# Sheet_PLC.net
KiCad netlist of a schematic drawn in Altium Designer
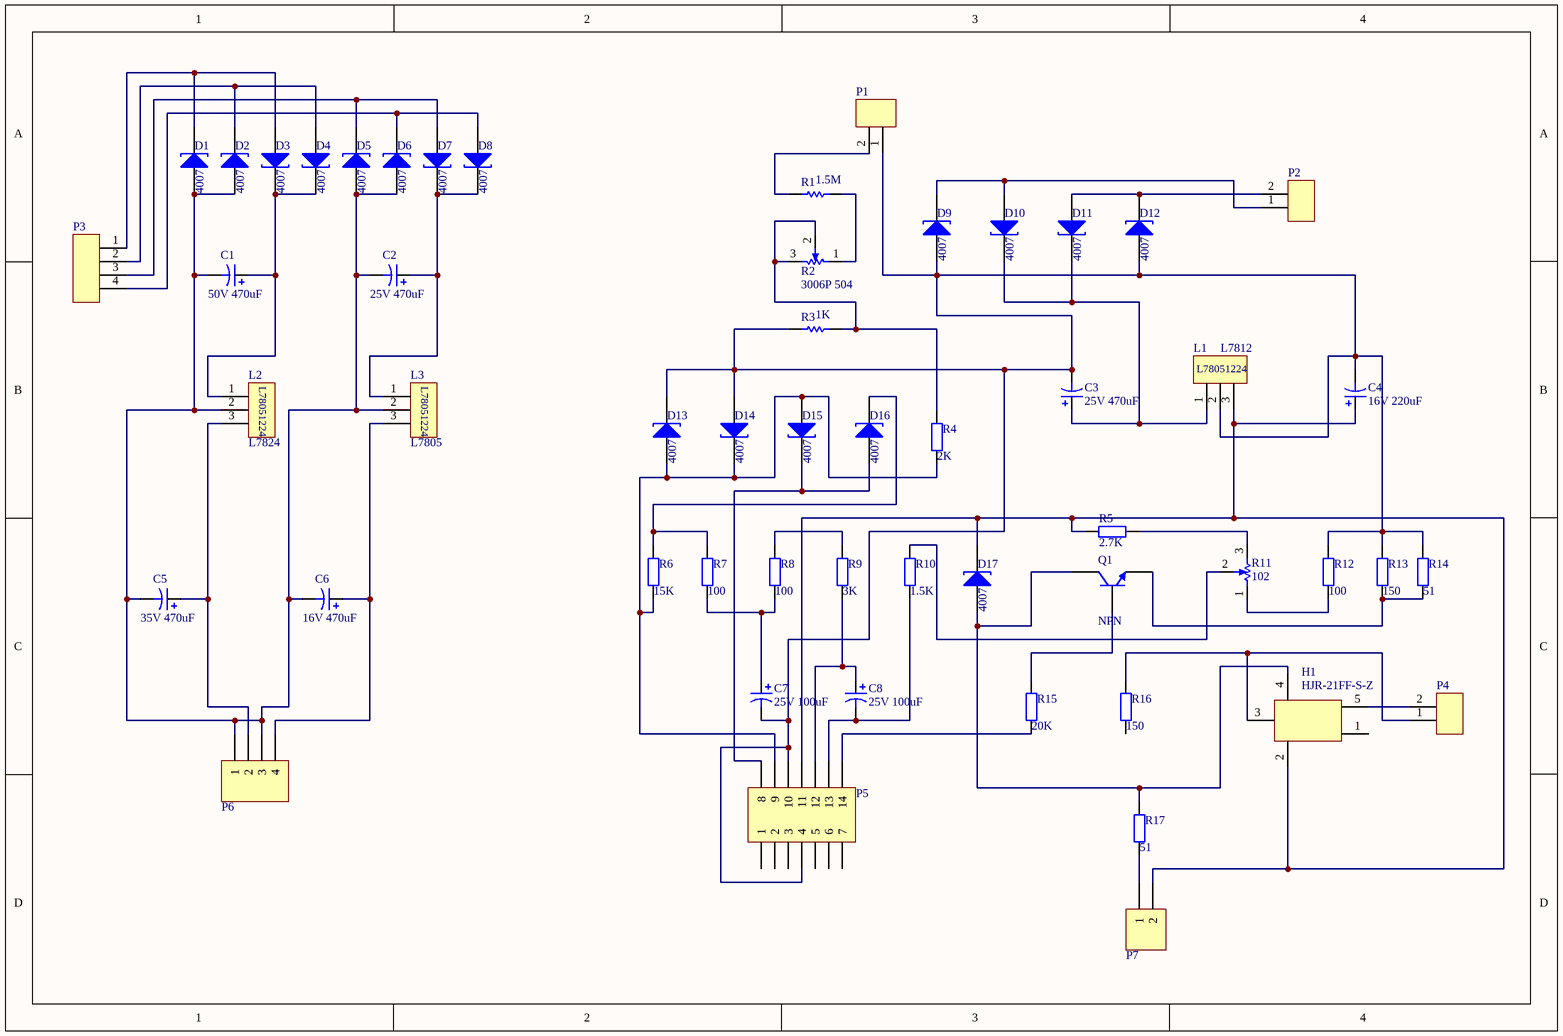
[diagram p0: Sheet_PLC.SchDoc]

(export (version "E")
  (design (tool "Eeschema 10.0.6"))
  (components
    (comp (ref "C1")
      (value "50V 470uF")
      (footprint "RB7.6-15")
      (description "Polarized Capacitor (Radial)")
      (fields (field (name "Comment") "Cap Pol1") (field (name "PUBLISHER") "Altium Limited"))
      (libsource (lib "Miscellaneous Devices") (part "Cap Pol1"))
    )
    (comp (ref "C2")
      (value "25V 470uF")
      (footprint "RB7.6-15")
      (description "Polarized Capacitor (Radial)")
      (fields (field (name "Comment") "Cap Pol1") (field (name "PUBLISHER") "Altium Limited"))
      (libsource (lib "Miscellaneous Devices") (part "Cap Pol1"))
    )
    (comp (ref "C3")
      (value "25V 470uF")
      (footprint "RB7.6-15")
      (description "Polarized Capacitor (Radial)")
      (fields (field (name "Comment") "Cap Pol1") (field (name "PUBLISHER") "Altium Limited"))
      (libsource (lib "Miscellaneous Devices") (part "Cap Pol1"))
    )
    (comp (ref "C4")
      (value "16V 220uF")
      (footprint "RB7.6-15")
      (description "Polarized Capacitor (Radial)")
      (fields (field (name "Comment") "Cap Pol1") (field (name "PUBLISHER") "Altium Limited"))
      (libsource (lib "Miscellaneous Devices") (part "Cap Pol1"))
    )
    (comp (ref "C5")
      (value "35V 470uF")
      (footprint "RB7.6-15")
      (description "Polarized Capacitor (Radial)")
      (fields (field (name "Comment") "Cap Pol1") (field (name "PUBLISHER") "Altium Limited"))
      (libsource (lib "Miscellaneous Devices") (part "Cap Pol1"))
    )
    (comp (ref "C6")
      (value "16V 470uF")
      (footprint "RB7.6-15")
      (description "Polarized Capacitor (Radial)")
      (fields (field (name "Comment") "Cap Pol1") (field (name "PUBLISHER") "Altium Limited"))
      (libsource (lib "Miscellaneous Devices") (part "Cap Pol1"))
    )
    (comp (ref "C7")
      (value "25V 100uF")
      (footprint "RB7.6-15")
      (description "Polarized Capacitor (Radial)")
      (fields (field (name "Comment") "Cap Pol1") (field (name "PUBLISHER") "Altium Limited"))
      (libsource (lib "Miscellaneous Devices") (part "Cap Pol1"))
    )
    (comp (ref "C8")
      (value "25V 100uF")
      (footprint "RB7.6-15")
      (description "Polarized Capacitor (Radial)")
      (fields (field (name "Comment") "Cap Pol1") (field (name "PUBLISHER") "Altium Limited"))
      (libsource (lib "Miscellaneous Devices") (part "Cap Pol1"))
    )
    (comp (ref "D1")
      (value "4007")
      (footprint "DIODE-0.4")
      (description "Tunnel Diode - Dependent Source Model")
      (fields (field (name "PUBLISHER") "Altium Limited"))
      (libsource (lib "Miscellaneous Devices") (part "D Tunnel2"))
    )
    (comp (ref "D2")
      (value "4007")
      (footprint "DIODE-0.4")
      (description "Tunnel Diode - Dependent Source Model")
      (fields (field (name "PUBLISHER") "Altium Limited"))
      (libsource (lib "Miscellaneous Devices") (part "D Tunnel2"))
    )
    (comp (ref "D3")
      (value "4007")
      (footprint "DIODE-0.4")
      (description "Tunnel Diode - Dependent Source Model")
      (fields (field (name "PUBLISHER") "Altium Limited"))
      (libsource (lib "Miscellaneous Devices") (part "D Tunnel2"))
    )
    (comp (ref "D4")
      (value "4007")
      (footprint "DIODE-0.4")
      (description "Tunnel Diode - Dependent Source Model")
      (fields (field (name "PUBLISHER") "Altium Limited"))
      (libsource (lib "Miscellaneous Devices") (part "D Tunnel2"))
    )
    (comp (ref "D5")
      (value "4007")
      (footprint "DIODE-0.4")
      (description "Tunnel Diode - Dependent Source Model")
      (fields (field (name "PUBLISHER") "Altium Limited"))
      (libsource (lib "Miscellaneous Devices") (part "D Tunnel2"))
    )
    (comp (ref "D6")
      (value "4007")
      (footprint "DIODE-0.4")
      (description "Tunnel Diode - Dependent Source Model")
      (fields (field (name "PUBLISHER") "Altium Limited"))
      (libsource (lib "Miscellaneous Devices") (part "D Tunnel2"))
    )
    (comp (ref "D7")
      (value "4007")
      (footprint "DIODE-0.4")
      (description "Tunnel Diode - Dependent Source Model")
      (fields (field (name "PUBLISHER") "Altium Limited"))
      (libsource (lib "Miscellaneous Devices") (part "D Tunnel2"))
    )
    (comp (ref "D8")
      (value "4007")
      (footprint "DIODE-0.4")
      (description "Tunnel Diode - Dependent Source Model")
      (fields (field (name "PUBLISHER") "Altium Limited"))
      (libsource (lib "Miscellaneous Devices") (part "D Tunnel2"))
    )
    (comp (ref "D9")
      (value "4007")
      (footprint "DIODE-0.4")
      (description "Tunnel Diode - Dependent Source Model")
      (fields (field (name "PUBLISHER") "Altium Limited"))
      (libsource (lib "Miscellaneous Devices") (part "D Tunnel2"))
    )
    (comp (ref "D10")
      (value "4007")
      (footprint "DIODE-0.4")
      (description "Tunnel Diode - Dependent Source Model")
      (fields (field (name "PUBLISHER") "Altium Limited"))
      (libsource (lib "Miscellaneous Devices") (part "D Tunnel2"))
    )
    (comp (ref "D11")
      (value "4007")
      (footprint "DIODE-0.4")
      (description "Tunnel Diode - Dependent Source Model")
      (fields (field (name "PUBLISHER") "Altium Limited"))
      (libsource (lib "Miscellaneous Devices") (part "D Tunnel2"))
    )
    (comp (ref "D12")
      (value "4007")
      (footprint "DIODE-0.4")
      (description "Tunnel Diode - Dependent Source Model")
      (fields (field (name "PUBLISHER") "Altium Limited"))
      (libsource (lib "Miscellaneous Devices") (part "D Tunnel2"))
    )
    (comp (ref "D13")
      (value "4007")
      (footprint "DIODE-0.4")
      (description "Tunnel Diode - Dependent Source Model")
      (fields (field (name "PUBLISHER") "Altium Limited"))
      (libsource (lib "Miscellaneous Devices") (part "D Tunnel2"))
    )
    (comp (ref "D14")
      (value "4007")
      (footprint "DIODE-0.4")
      (description "Tunnel Diode - Dependent Source Model")
      (fields (field (name "PUBLISHER") "Altium Limited"))
      (libsource (lib "Miscellaneous Devices") (part "D Tunnel2"))
    )
    (comp (ref "D15")
      (value "4007")
      (footprint "DIODE-0.4")
      (description "Tunnel Diode - Dependent Source Model")
      (fields (field (name "PUBLISHER") "Altium Limited"))
      (libsource (lib "Miscellaneous Devices") (part "D Tunnel2"))
    )
    (comp (ref "D16")
      (value "4007")
      (footprint "DIODE-0.4")
      (description "Tunnel Diode - Dependent Source Model")
      (fields (field (name "PUBLISHER") "Altium Limited"))
      (libsource (lib "Miscellaneous Devices") (part "D Tunnel2"))
    )
    (comp (ref "D17")
      (value "4007")
      (footprint "DIODE-0.4")
      (description "Tunnel Diode - Dependent Source Model")
      (fields (field (name "PUBLISHER") "Altium Limited"))
      (libsource (lib "Miscellaneous Devices") (part "D Tunnel2"))
    )
    (comp (ref "H1")
      (value "HJR-21FF-S-Z")
      (footprint "HJR-21FF-S-Z 12V")
      (libsource (lib "Schlib_PLC") (part "HJR-21FF-S-Z"))
    )
    (comp (ref "L1")
      (value "L7812")
      (footprint "L78051224")
      (libsource (lib "Schlib_PLC") (part "L78051224"))
    )
    (comp (ref "L2") (value "L7824") (footprint "L78051224") (libsource (lib "") (part "L78051224_1")))
    (comp (ref "L3") (value "L7805") (footprint "L78051224") (libsource (lib "") (part "L78051224_1")))
    (comp (ref "P1") (value "CH3.96 2P") (footprint "CH3.96 2P") (libsource (lib "") (part "CH3.96 2P_1")))
    (comp (ref "P2")
      (value "CH3.96 2P")
      (footprint "CH3.96 2P")
      (libsource (lib "Schlib_PLC") (part "CH3.96 2P"))
    )
    (comp (ref "P3")
      (value "CH3.96 4P")
      (footprint "CH3.96 4P")
      (libsource (lib "Schlib_PLC") (part "CH3.96 4P"))
    )
    (comp (ref "P4")
      (value "CH3.96 2P")
      (footprint "CH3.96 2P")
      (libsource (lib "Schlib_PLC") (part "CH3.96 2P"))
    )
    (comp (ref "P5")
      (value "Header 7X2A")
      (footprint "Header 7X2A")
      (description "Header, 7-Pin, Dual row")
      (fields (field (name "PUBLISHER") "Altium Limited"))
      (libsource (lib "Miscellaneous Connectors") (part "Header 7X2A"))
    )
    (comp (ref "P6")
      (value "Header 4")
      (footprint "HDRR1X4")
      (description "Header, 4-Pin")
      (fields (field (name "PUBLISHER") "Altium Limited"))
      (libsource (lib "Miscellaneous Connectors") (part "Header 4"))
    )
    (comp (ref "P7")
      (value "Header 2")
      (footprint "HDRR1X2")
      (description "Header, 2-Pin")
      (fields (field (name "PUBLISHER") "Altium Limited"))
      (libsource (lib "Miscellaneous Connectors") (part "Header 2"))
    )
    (comp (ref "Q1")
      (value "NPN")
      (footprint "S0914")
      (description "NPN Bipolar Transistor")
      (fields (field (name "PUBLISHER") "Altium Limited"))
      (libsource (lib "Miscellaneous Devices") (part "NPN"))
    )
    (comp (ref "R1")
      (value "1.5M")
      (footprint "R1.5M1W")
      (description "Resistor")
      (fields (field (name "Comment") "Res1") (field (name "PUBLISHER") "Altium Limited"))
      (libsource (lib "Miscellaneous Devices") (part "Res1"))
    )
    (comp (ref "R2")
      (value "3006P 504")
      (footprint "R504")
      (description "Square Trimming Potentiometer")
      (fields (field (name "PUBLISHER") "Altium Limited"))
      (libsource (lib "Schlib_PLC") (part "RPot SM_1"))
    )
    (comp (ref "R3")
      (value "1K")
      (footprint "R1K1W")
      (description "Resistor")
      (fields (field (name "Comment") "Res1") (field (name "PUBLISHER") "Altium Limited"))
      (libsource (lib "Miscellaneous Devices") (part "Res1"))
    )
    (comp (ref "R4")
      (value "2K")
      (footprint "AXIAL-0.4")
      (description "Resistor")
      (fields (field (name "Comment") "Res2") (field (name "PUBLISHER") "Altium Limited"))
      (libsource (lib "Miscellaneous Devices") (part "Res2"))
    )
    (comp (ref "R5")
      (value "2.7K")
      (footprint "AXIAL-0.4")
      (description "Resistor")
      (fields (field (name "Comment") "Res2") (field (name "PUBLISHER") "Altium Limited"))
      (libsource (lib "") (part "Res2_1"))
    )
    (comp (ref "R6")
      (value "15K")
      (footprint "AXIAL-0.4")
      (description "Resistor")
      (fields (field (name "Comment") "Res2") (field (name "PUBLISHER") "Altium Limited"))
      (libsource (lib "Miscellaneous Devices") (part "Res2"))
    )
    (comp (ref "R7")
      (value "100")
      (footprint "AXIAL-0.4")
      (description "Resistor")
      (fields (field (name "Comment") "Res2") (field (name "PUBLISHER") "Altium Limited"))
      (libsource (lib "Miscellaneous Devices") (part "Res2"))
    )
    (comp (ref "R8")
      (value "100")
      (footprint "AXIAL-0.4")
      (description "Resistor")
      (fields (field (name "Comment") "Res2") (field (name "PUBLISHER") "Altium Limited"))
      (libsource (lib "Miscellaneous Devices") (part "Res2"))
    )
    (comp (ref "R9")
      (value "3K")
      (footprint "AXIAL-0.4")
      (description "Resistor")
      (fields (field (name "Comment") "Res2") (field (name "PUBLISHER") "Altium Limited"))
      (libsource (lib "Miscellaneous Devices") (part "Res2"))
    )
    (comp (ref "R10")
      (value "1.5K")
      (footprint "AXIAL-0.4")
      (description "Resistor")
      (fields (field (name "Comment") "Res2") (field (name "PUBLISHER") "Altium Limited"))
      (libsource (lib "Miscellaneous Devices") (part "Res2"))
    )
    (comp (ref "R11")
      (value "102")
      (footprint "R102")
      (description "Square Trimming Potentiometer")
      (fields (field (name "PUBLISHER") "Altium Limited"))
      (libsource (lib "Schlib_PLC") (part "RPot SM"))
    )
    (comp (ref "R12")
      (value "100")
      (footprint "AXIAL-0.4")
      (description "Resistor")
      (fields (field (name "Comment") "Res2") (field (name "PUBLISHER") "Altium Limited"))
      (libsource (lib "Miscellaneous Devices") (part "Res2"))
    )
    (comp (ref "R13")
      (value "150")
      (footprint "AXIAL-0.4")
      (description "Resistor")
      (fields (field (name "Comment") "Res2") (field (name "PUBLISHER") "Altium Limited"))
      (libsource (lib "Miscellaneous Devices") (part "Res2"))
    )
    (comp (ref "R14")
      (value "51")
      (footprint "AXIAL-0.4")
      (description "Resistor")
      (fields (field (name "Comment") "Res2") (field (name "PUBLISHER") "Altium Limited"))
      (libsource (lib "Miscellaneous Devices") (part "Res2"))
    )
    (comp (ref "R15")
      (value "20K")
      (footprint "AXIAL-0.4")
      (description "Resistor")
      (fields (field (name "Comment") "Res2") (field (name "PUBLISHER") "Altium Limited"))
      (libsource (lib "Miscellaneous Devices") (part "Res2"))
    )
    (comp (ref "R16")
      (value "150")
      (footprint "AXIAL-0.4")
      (description "Resistor")
      (fields (field (name "Comment") "Res2") (field (name "PUBLISHER") "Altium Limited"))
      (libsource (lib "Miscellaneous Devices") (part "Res2"))
    )
    (comp (ref "R17")
      (value "51")
      (footprint "AXIAL-0.4")
      (description "Resistor")
      (fields (field (name "Comment") "Res2") (field (name "PUBLISHER") "Altium Limited"))
      (libsource (lib "Miscellaneous Devices") (part "Res2"))
    )
  )
  (nets
    (net (code "1") (name "Net-(C5-Pad1)") (class "Default")
      (node (ref "C5") (pin "1") (pinfunction "1_1") (pintype "passive"))
      (node (ref "L2") (pin "3") (pinfunction "3_3") (pintype "passive"))
      (node (ref "P6") (pin "2") (pinfunction "2_2") (pintype "passive"))
    )
    (net (code "2") (name "Net-(C6-Pad1)") (class "Default")
      (node (ref "C6") (pin "1") (pinfunction "1_1") (pintype "passive"))
      (node (ref "L3") (pin "3") (pinfunction "3_3") (pintype "passive"))
      (node (ref "P6") (pin "4") (pinfunction "4_4") (pintype "passive"))
    )
    (net (code "3") (name "Net-(C7-Pad1)") (class "Default")
      (node (ref "C7") (pin "1") (pinfunction "1_1") (pintype "passive"))
      (node (ref "R7") (pin "1") (pinfunction "1_1") (pintype "passive"))
      (node (ref "R8") (pin "1") (pinfunction "1_1") (pintype "passive"))
    )
    (net (code "4") (name "Net-(C8-Pad1)") (class "Default")
      (node (ref "C8") (pin "1") (pinfunction "1_1") (pintype "passive"))
      (node (ref "P5") (pin "12") (pinfunction "12_12") (pintype "passive"))
      (node (ref "R9") (pin "1") (pinfunction "1_1") (pintype "passive"))
    )
    (net (code "5") (name "Net-(C8-Pad2)") (class "Default")
      (node (ref "C8") (pin "2") (pinfunction "2_2") (pintype "passive"))
      (node (ref "P5") (pin "13") (pinfunction "13_13") (pintype "passive"))
      (node (ref "R10") (pin "1") (pinfunction "1_1") (pintype "passive"))
    )
    (net (code "6") (name "Net-(D1-A)") (class "Default")
      (node (ref "C1") (pin "2") (pinfunction "2_2") (pintype "passive"))
      (node (ref "C2") (pin "2") (pinfunction "2_2") (pintype "passive"))
      (node (ref "C5") (pin "2") (pinfunction "2_2") (pintype "passive"))
      (node (ref "C6") (pin "2") (pinfunction "2_2") (pintype "passive"))
      (node (ref "D1") (pin "1") (pinfunction "A_1") (pintype "passive"))
      (node (ref "D2") (pin "1") (pinfunction "A_1") (pintype "passive"))
      (node (ref "D5") (pin "1") (pinfunction "A_1") (pintype "passive"))
      (node (ref "D6") (pin "1") (pinfunction "A_1") (pintype "passive"))
      (node (ref "L2") (pin "2") (pinfunction "2_2") (pintype "passive"))
      (node (ref "L3") (pin "2") (pinfunction "2_2") (pintype "passive"))
      (node (ref "P6") (pin "1") (pinfunction "1_1") (pintype "passive"))
      (node (ref "P6") (pin "3") (pinfunction "3_3") (pintype "passive"))
    )
    (net (code "7") (name "Net-(D1-K)") (class "Default")
      (node (ref "D1") (pin "2") (pinfunction "K_2") (pintype "passive"))
      (node (ref "D3") (pin "1") (pinfunction "A_1") (pintype "passive"))
      (node (ref "P3") (pin "1") (pinfunction "1_1") (pintype "passive"))
    )
    (net (code "8") (name "Net-(D2-K)") (class "Default")
      (node (ref "D2") (pin "2") (pinfunction "K_2") (pintype "passive"))
      (node (ref "D4") (pin "1") (pinfunction "A_1") (pintype "passive"))
      (node (ref "P3") (pin "2") (pinfunction "2_2") (pintype "passive"))
    )
    (net (code "9") (name "Net-(D3-K)") (class "Default")
      (node (ref "C1") (pin "1") (pinfunction "1_1") (pintype "passive"))
      (node (ref "D3") (pin "2") (pinfunction "K_2") (pintype "passive"))
      (node (ref "D4") (pin "2") (pinfunction "K_2") (pintype "passive"))
      (node (ref "L2") (pin "1") (pinfunction "1_1") (pintype "passive"))
    )
    (net (code "10") (name "Net-(D5-K)") (class "Default")
      (node (ref "D5") (pin "2") (pinfunction "K_2") (pintype "passive"))
      (node (ref "D7") (pin "1") (pinfunction "A_1") (pintype "passive"))
      (node (ref "P3") (pin "3") (pinfunction "3_3") (pintype "passive"))
    )
    (net (code "11") (name "Net-(D6-K)") (class "Default")
      (node (ref "D6") (pin "2") (pinfunction "K_2") (pintype "passive"))
      (node (ref "D8") (pin "1") (pinfunction "A_1") (pintype "passive"))
      (node (ref "P3") (pin "4") (pinfunction "4_4") (pintype "passive"))
    )
    (net (code "12") (name "Net-(D7-K)") (class "Default")
      (node (ref "C2") (pin "1") (pinfunction "1_1") (pintype "passive"))
      (node (ref "D7") (pin "2") (pinfunction "K_2") (pintype "passive"))
      (node (ref "D8") (pin "2") (pinfunction "K_2") (pintype "passive"))
      (node (ref "L3") (pin "1") (pinfunction "1_1") (pintype "passive"))
    )
    (net (code "13") (name "Net-(D10-A)") (class "Default")
      (node (ref "D10") (pin "1") (pinfunction "A_1") (pintype "passive"))
      (node (ref "D9") (pin "2") (pinfunction "K_2") (pintype "passive"))
      (node (ref "P2") (pin "1") (pinfunction "1_1") (pintype "passive"))
    )
    (net (code "14") (name "Net-(D10-K)") (class "Default")
      (node (ref "C3") (pin "1") (pinfunction "1_1") (pintype "passive"))
      (node (ref "D10") (pin "2") (pinfunction "K_2") (pintype "passive"))
      (node (ref "D11") (pin "2") (pinfunction "K_2") (pintype "passive"))
      (node (ref "L1") (pin "1") (pinfunction "1_1") (pintype "passive"))
    )
    (net (code "15") (name "Net-(D11-A)") (class "Default")
      (node (ref "D11") (pin "1") (pinfunction "A_1") (pintype "passive"))
      (node (ref "D12") (pin "2") (pinfunction "K_2") (pintype "passive"))
      (node (ref "P2") (pin "2") (pinfunction "2_2") (pintype "passive"))
    )
    (net (code "16") (name "Net-(D12-A)") (class "Default")
      (node (ref "C3") (pin "2") (pinfunction "2_2") (pintype "passive"))
      (node (ref "C4") (pin "2") (pinfunction "2_2") (pintype "passive"))
      (node (ref "C7") (pin "2") (pinfunction "2_2") (pintype "passive"))
      (node (ref "D12") (pin "1") (pinfunction "A_1") (pintype "passive"))
      (node (ref "D13") (pin "2") (pinfunction "K_2") (pintype "passive"))
      (node (ref "D14") (pin "1") (pinfunction "A_1") (pintype "passive"))
      (node (ref "D9") (pin "1") (pinfunction "A_1") (pintype "passive"))
      (node (ref "L1") (pin "2") (pinfunction "2_2") (pintype "passive"))
      (node (ref "P1") (pin "1") (pinfunction "1_1") (pintype "passive"))
      (node (ref "P5") (pin "10") (pinfunction "10_10") (pintype "passive"))
      (node (ref "P5") (pin "4") (pinfunction "4_4") (pintype "passive"))
      (node (ref "R12") (pin "2") (pinfunction "2_2") (pintype "passive"))
      (node (ref "R13") (pin "2") (pinfunction "2_2") (pintype "passive"))
      (node (ref "R14") (pin "2") (pinfunction "2_2") (pintype "passive"))
      (node (ref "R3") (pin "1") (pinfunction "1_1") (pintype "passive"))
    )
    (net (code "17") (name "Net-(D13-A)") (class "Default")
      (node (ref "D13") (pin "1") (pinfunction "A_1") (pintype "passive"))
      (node (ref "D14") (pin "2") (pinfunction "K_2") (pintype "passive"))
      (node (ref "D15") (pin "1") (pinfunction "A_1") (pintype "passive"))
      (node (ref "P5") (pin "9") (pinfunction "9_9") (pintype "passive"))
      (node (ref "R4") (pin "1") (pinfunction "1_1") (pintype "passive"))
      (node (ref "R6") (pin "1") (pinfunction "1_1") (pintype "passive"))
    )
    (net (code "18") (name "Net-(D15-K)") (class "Default")
      (node (ref "D15") (pin "2") (pinfunction "K_2") (pintype "passive"))
      (node (ref "D16") (pin "1") (pinfunction "A_1") (pintype "passive"))
      (node (ref "P5") (pin "8") (pinfunction "8_8") (pintype "passive"))
    )
    (net (code "19") (name "Net-(D16-K)") (class "Default")
      (node (ref "D16") (pin "2") (pinfunction "K_2") (pintype "passive"))
      (node (ref "R6") (pin "2") (pinfunction "2_2") (pintype "passive"))
      (node (ref "R7") (pin "2") (pinfunction "2_2") (pintype "passive"))
    )
    (net (code "20") (name "Net-(D17-A)") (class "Default")
      (node (ref "D17") (pin "1") (pinfunction "A_1") (pintype "passive"))
      (node (ref "H1") (pin "4") (pinfunction "4_4") (pintype "passive"))
      (node (ref "Q1") (pin "1") (pinfunction "C_1") (pintype "passive"))
      (node (ref "R17") (pin "2") (pinfunction "2_2") (pintype "passive"))
    )
    (net (code "21") (name "Net-(D17-K)") (class "Default")
      (node (ref "C4") (pin "1") (pinfunction "1_1") (pintype "passive"))
      (node (ref "D17") (pin "2") (pinfunction "K_2") (pintype "passive"))
      (node (ref "H1") (pin "2") (pinfunction "2_2") (pintype "passive"))
      (node (ref "L1") (pin "3") (pinfunction "3_3") (pintype "passive"))
      (node (ref "P5") (pin "11") (pinfunction "11_11") (pintype "passive"))
      (node (ref "P7") (pin "2") (pinfunction "2_2") (pintype "passive"))
      (node (ref "R5") (pin "2") (pinfunction "2_2") (pintype "passive"))
    )
    (net (code "22") (name "Net-(H1-Pad3)") (class "Default")
      (node (ref "H1") (pin "3") (pinfunction "3_3") (pintype "passive"))
      (node (ref "P4") (pin "1") (pinfunction "1_1") (pintype "passive"))
      (node (ref "R16") (pin "2") (pinfunction "2_2") (pintype "passive"))
    )
    (net (code "23") (name "Net-(H1-Pad5)") (class "Default")
      (node (ref "H1") (pin "5") (pinfunction "5_5") (pintype "passive"))
      (node (ref "P4") (pin "2") (pinfunction "2_2") (pintype "passive"))
    )
    (net (code "24") (name "Net-(P1-Pad2)") (class "Default")
      (node (ref "P1") (pin "2") (pinfunction "2_2") (pintype "passive"))
      (node (ref "R1") (pin "1") (pinfunction "1_1") (pintype "passive"))
    )
    (net (code "25") (name "Net-(P5-Pad14)") (class "Default")
      (node (ref "P5") (pin "14") (pinfunction "14_14") (pintype "passive"))
      (node (ref "R15") (pin "1") (pinfunction "1_1") (pintype "passive"))
    )
    (net (code "26") (name "Net-(P7-Pad1)") (class "Default")
      (node (ref "P7") (pin "1") (pinfunction "1_1") (pintype "passive"))
      (node (ref "R17") (pin "1") (pinfunction "1_1") (pintype "passive"))
    )
    (net (code "27") (name "Net-(Q1-B)") (class "Default")
      (node (ref "Q1") (pin "2") (pinfunction "B_2") (pintype "passive"))
      (node (ref "R15") (pin "2") (pinfunction "2_2") (pintype "passive"))
    )
    (net (code "28") (name "Net-(Q1-E)") (class "Default")
      (node (ref "Q1") (pin "3") (pinfunction "E_3") (pintype "passive"))
      (node (ref "R13") (pin "1") (pinfunction "1_1") (pintype "passive"))
      (node (ref "R14") (pin "1") (pinfunction "1_1") (pintype "passive"))
    )
    (net (code "29") (name "Net-(R1-Pad2)") (class "Default")
      (node (ref "R1") (pin "2") (pinfunction "2_2") (pintype "passive"))
      (node (ref "R2") (pin "1") (pinfunction "1_1") (pintype "passive"))
    )
    (net (code "30") (name "Net-(R2-Pad2)") (class "Default")
      (node (ref "R2") (pin "2") (pinfunction "2_2") (pintype "passive"))
      (node (ref "R2") (pin "3") (pinfunction "3_3") (pintype "passive"))
      (node (ref "R3") (pin "2") (pinfunction "2_2") (pintype "passive"))
      (node (ref "R4") (pin "2") (pinfunction "2_2") (pintype "passive"))
    )
    (net (code "31") (name "Net-(R8-Pad2)") (class "Default")
      (node (ref "R8") (pin "2") (pinfunction "2_2") (pintype "passive"))
      (node (ref "R9") (pin "2") (pinfunction "2_2") (pintype "passive"))
    )
    (net (code "32") (name "Net-(R10-Pad2)") (class "Default")
      (node (ref "R10") (pin "2") (pinfunction "2_2") (pintype "passive"))
      (node (ref "R11") (pin "2") (pinfunction "2_2") (pintype "passive"))
    )
    (net (code "33") (name "Net-(R11-Pad1)") (class "Default")
      (node (ref "R11") (pin "1") (pinfunction "1_1") (pintype "passive"))
      (node (ref "R12") (pin "1") (pinfunction "1_1") (pintype "passive"))
    )
    (net (code "34") (name "Net-(R11-Pad3)") (class "Default")
      (node (ref "R11") (pin "3") (pinfunction "3_3") (pintype "passive"))
      (node (ref "R5") (pin "1") (pinfunction "1_1") (pintype "passive"))
    )
    (net (code "35") (name "unconnected-(H1-Pad1)") (class "Default")
      (node (ref "H1") (pin "1") (pinfunction "1_1") (pintype "passive"))
    )
    (net (code "36") (name "unconnected-(P5-Pad1)") (class "Default")
      (node (ref "P5") (pin "1") (pinfunction "1_1") (pintype "passive"))
    )
    (net (code "37") (name "unconnected-(P5-Pad2)") (class "Default")
      (node (ref "P5") (pin "2") (pinfunction "2_2") (pintype "passive"))
    )
    (net (code "38") (name "unconnected-(P5-Pad3)") (class "Default")
      (node (ref "P5") (pin "3") (pinfunction "3_3") (pintype "passive"))
    )
    (net (code "39") (name "unconnected-(P5-Pad5)") (class "Default")
      (node (ref "P5") (pin "5") (pinfunction "5_5") (pintype "passive"))
    )
    (net (code "40") (name "unconnected-(P5-Pad6)") (class "Default")
      (node (ref "P5") (pin "6") (pinfunction "6_6") (pintype "passive"))
    )
    (net (code "41") (name "unconnected-(P5-Pad7)") (class "Default")
      (node (ref "P5") (pin "7") (pinfunction "7_7") (pintype "passive"))
    )
    (net (code "42") (name "unconnected-(R16-Pad1)") (class "Default")
      (node (ref "R16") (pin "1") (pinfunction "1_1") (pintype "passive"))
    )
  )
)
